# Power_tree_design.net
KiCad netlist of a schematic drawn in Altium Designer
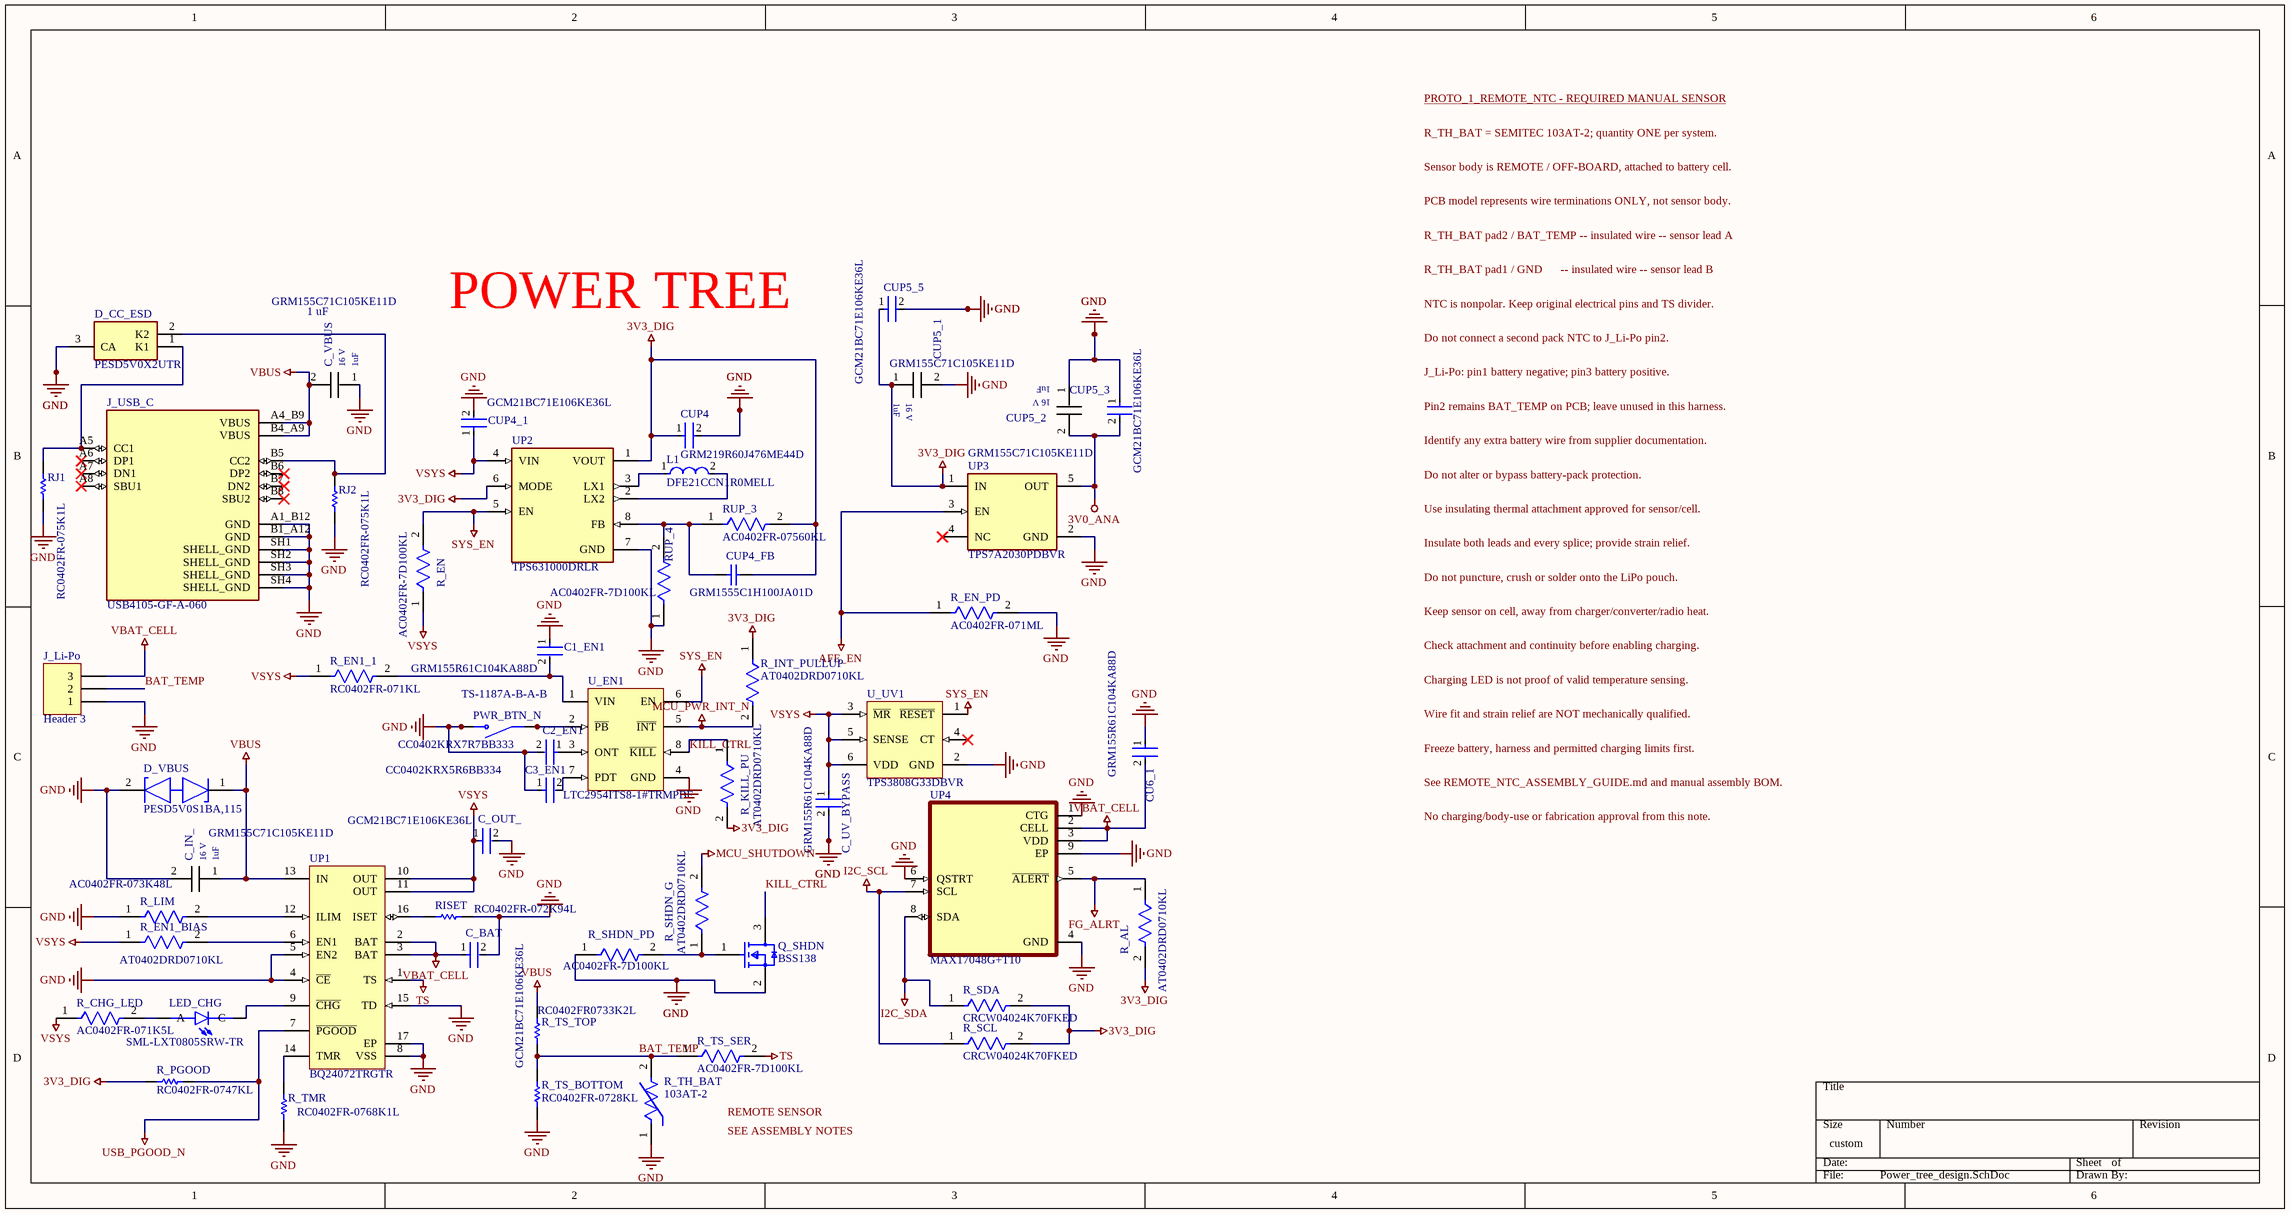
[diagram p0: Power_tree_design.SchDoc]

(export (version "E")
  (design (tool "Eeschema 10.0.6"))
  (components
    (comp (ref "C1_EN1")
      (value "GRM155R61C104KA88D")
      (footprint "96DF66F8-B997-472F-A885-42BCAAE661B2_FP-GRM155-0_05-IPC_C:FP-GRM155-0_05-IPC_C")
      (description "CAP CER 0.1UF 16V X5R 0402")
      (fields (field (name "VOLTAGE") "16V") (field (name "TOLERANCE") "10%"))
      (libsource (lib "EMG_Controlled_R5") (part "EMG_R5_C1_EN1"))
    )
    (comp (ref "C2_EN1")
      (value "CC0402KRX7R7BB333")
      (footprint "C3796861-3712-47DF-AA44-4C1CD1021AF7_FP-CC0402-MFG:FP-CC0402-MFG")
      (description "CAP CER 0.033UF 16V X7R 0402")
      (fields
        (field (name "MANUFACTURER") "YAGEO")
        (field (name "OCTOPART") "https://octopart.com/cc0402krx7r7bb333-yageo-9289202")
      )
      (libsource (lib "EMG_Controlled_R5") (part "EMG_R5_C2_EN1"))
    )
    (comp (ref "C3_EN1")
      (value "CC0402KRX5R6BB334")
      (footprint "C3796861-3712-47DF-AA44-4C1CD1021AF7_FP-CC0402-MFG:FP-CC0402-MFG")
      (description "CAP CER 0.33UF 10V X5R 0402")
      (fields
        (field (name "MANUFACTURER") "YAGEO")
        (field (name "OCTOPART") "https://octopart.com/cc0402krx5r6bb334-yageo-21548561")
      )
      (libsource (lib "EMG_Controlled_R5") (part "EMG_R5_C3_EN1"))
    )
    (comp (ref "CU6_1")
      (value "GRM155R61C104KA88D")
      (footprint "96DF66F8-B997-472F-A885-42BCAAE661B2_FP-GRM155-0_05-IPC_C:FP-GRM155-0_05-IPC_C")
      (description "CAP CER 0.1UF 16V X5R 0402")
      (fields (field (name "VOLTAGE") "16V") (field (name "TOLERANCE") "10%"))
      (libsource (lib "EMG_Controlled_R5") (part "EMG_R5_CU6_1"))
    )
    (comp (ref "CUP4")
      (value "GRM219R60J476ME44D")
      (footprint "C53EA0CA-0507-449B-AA9E-0712004E71D5_FP-GRM219-0_2-0_1-IPC_A:FP-GRM219-0_2-0_1-IPC_A")
      (description "Chip Multilayer Ceramic Capacitors for General Purpose, 0805, 47uF, X5R, 15%, 20%, 6.3V")
      (fields (field (name "TOLERANCE") "20%"))
      (libsource (lib "EMG_Controlled_R5") (part "EMG_R5_CUP4"))
    )
    (comp (ref "CUP4_1")
      (value "GCM21BC71E106KE36L")
      (footprint "936D640C-6583-4BC1-90EC-E059FB2B465D_FP-GCM21B-0_2-e0_2_0_7-MFG:FP-GCM21B-0_2-e0_2_0_7-MFG")
      (description "10 µF ±10% 25V Ceramic Capacitor X7S 0805 (2012 Metric)")
      (libsource (lib "EMG_Controlled_R5") (part "EMG_R5_CUP4_1"))
    )
    (comp (ref "CUP4_FB")
      (value "GRM1555C1H100JA01D")
      (footprint "2E7254C8-59E0-43F9-ABB3-713B229FF2F1_CAPC1005X55X25LL05T10:CAPC1005X55X25LL05T10")
      (fields (field (name "MANUFACTURER") "Murata"))
      (libsource (lib "EMG_Controlled_R5") (part "EMG_R5_CUP4_FB"))
    )
    (comp (ref "CUP5_1")
      (value "GRM155C71C105KE11D")
      (footprint "MURATA_GRM155C71C105KE11D_0:*MURATA_GRM155C71C105KE11D_0")
      (description "Murata GRM155C71C105KE11D: 1 uF 16 V X7S +/-10%, 0402/1005 metric")
      (fields (field (name "MF") "Murata") (field (name "TOLERANCE") "+/-10%"))
      (libsource (lib "EMG_Controlled_R5") (part "EMG_R5_CUP5_1"))
    )
    (comp (ref "CUP5_2")
      (value "GRM155C71C105KE11D")
      (footprint "MURATA_GRM155C71C105KE11D_0:*MURATA_GRM155C71C105KE11D_0")
      (description "Murata GRM155C71C105KE11D: 1 uF 16 V X7S +/-10%, 0402/1005 metric")
      (fields (field (name "MF") "Murata") (field (name "TOLERANCE") "+/-10%"))
      (libsource (lib "EMG_Controlled_R5") (part "EMG_R5_CUP5_2"))
    )
    (comp (ref "CUP5_3")
      (value "GCM21BC71E106KE36L")
      (footprint "936D640C-6583-4BC1-90EC-E059FB2B465D_FP-GCM21B-0_2-e0_2_0_7-MFG:FP-GCM21B-0_2-e0_2_0_7-MFG")
      (description "10 µF ±10% 25V Ceramic Capacitor X7S 0805 (2012 Metric)")
      (libsource (lib "EMG_Controlled_R5") (part "EMG_R5_CUP5_3"))
    )
    (comp (ref "CUP5_5")
      (value "GCM21BC71E106KE36L")
      (footprint "936D640C-6583-4BC1-90EC-E059FB2B465D_FP-GCM21B-0_2-e0_2_0_7-MFG:FP-GCM21B-0_2-e0_2_0_7-MFG")
      (description "10 µF ±10% 25V Ceramic Capacitor X7S 0805 (2012 Metric)")
      (libsource (lib "EMG_Controlled_R5") (part "EMG_R5_CUP5_5"))
    )
    (comp (ref "C_BAT")
      (value "GCM21BC71E106KE36L")
      (footprint "936D640C-6583-4BC1-90EC-E059FB2B465D_FP-GCM21B-0_2-e0_2_0_7-MFG:FP-GCM21B-0_2-e0_2_0_7-MFG")
      (description "10 µF ±10% 25V Ceramic Capacitor X7S 0805 (2012 Metric)")
      (libsource (lib "EMG_Controlled_R5") (part "EMG_R5_C_BAT"))
    )
    (comp (ref "C_IN_")
      (value "GRM155C71C105KE11D")
      (footprint "MURATA_GRM155C71C105KE11D_0:*MURATA_GRM155C71C105KE11D_0")
      (description "Murata GRM155C71C105KE11D: 1 uF 16 V X7S +/-10%, 0402/1005 metric")
      (fields (field (name "MF") "Murata") (field (name "TOLERANCE") "+/-10%"))
      (libsource (lib "EMG_Controlled_R5") (part "EMG_R5_C_IN_"))
    )
    (comp (ref "C_OUT_")
      (value "GCM21BC71E106KE36L")
      (footprint "936D640C-6583-4BC1-90EC-E059FB2B465D_FP-GCM21B-0_2-e0_2_0_7-MFG:FP-GCM21B-0_2-e0_2_0_7-MFG")
      (description "10 µF ±10% 25V Ceramic Capacitor X7S 0805 (2012 Metric)")
      (libsource (lib "EMG_Controlled_R5") (part "EMG_R5_C_OUT_"))
    )
    (comp (ref "C_UV_BYPASS")
      (value "GRM155R61C104KA88D")
      (footprint "96DF66F8-B997-472F-A885-42BCAAE661B2_FP-GRM155-0_05-IPC_C:FP-GRM155-0_05-IPC_C")
      (description "CAP CER 0.1UF 16V X5R 0402")
      (fields (field (name "VOLTAGE") "16V") (field (name "TOLERANCE") "10%"))
      (libsource (lib "EMG_Controlled_R5") (part "EMG_R5_C_UV_BYPASS"))
    )
    (comp (ref "C_VBUS")
      (value "GRM155C71C105KE11D")
      (footprint "MURATA_GRM155C71C105KE11D_0:*MURATA_GRM155C71C105KE11D_0")
      (description "Murata GRM155C71C105KE11D: 1 uF 16 V X7S +/-10%, 0402/1005 metric")
      (fields
        (field (name "MF") "Murata")
        (field (name "ALTIUM_VALUE") "1 uF")
        (field (name "TOLERANCE") "+/-10%")
      )
      (libsource (lib "EMG_Controlled_R5") (part "EMG_R5_C_VBUS"))
    )
    (comp (ref "D_CC_ESD")
      (value "PESD5V0X2UTR")
      (footprint "SamacSys:SOT95P230X100-3N")
      (description "TVS Diode (Uni-directional)")
      (libsource (lib "EMG_Controlled_R5") (part "EMG_R5_D_CC_ESD"))
    )
    (comp (ref "D_VBUS")
      (value "PESD5V0S1BA,115")
      (footprint "45C21C89-16FD-4743-99D5-BE7C796D208F_FP-SOD323-CA-MFG:FP-SOD323-CA-MFG")
      (description "TVS DIODE 5V 14V SOD323")
      (libsource (lib "EMG_Controlled_R5") (part "EMG_R5_D_VBUS"))
    )
    (comp (ref "J_Li-Po")
      (value "Header 3")
      (footprint "Miscellaneous_Connectors_0:HDR1X3")
      (description "Header, 3-Pin")
      (fields (field (name "PUBLISHER") "Altium Limited"))
      (libsource (lib "EMG_Controlled_R5") (part "EMG_R5_J_Li-Po"))
    )
    (comp (ref "J_USB_C")
      (value "USB4105-GF-A-060")
      (footprint "USB4105-GF-A-060_0:GCT_USB4105-GF-A-060")
      (fields (field (name "MF") "Global Connector Technology") (field (name "MP") "USB4105GFA060"))
      (libsource (lib "EMG_Controlled_R5") (part "EMG_R5_J_USB_C"))
    )
    (comp (ref "L1")
      (value "DFE21CCN1R0MELL")
      (footprint "F49AD27E-DF89-41E7-B4E0-151C9F468E9A_FP-DFE21CC_EL-MFG:FP-DFE21CC_EL-MFG")
      (description "FIXED IND 1.0UH 3300MA NONAUTO")
      (libsource (lib "EMG_Controlled_R5") (part "EMG_R5_L1"))
    )
    (comp (ref "LED_CHG")
      (value "SML-LXT0805SRW-TR")
      (footprint "SML-LXT0805SRW-TR_0:LEDC2012X120N")
      (description "Red - LED Indication - Discrete 1.8V 0805 (2012 Metric)")
      (fields (field (name "MF") "Lumex Opto/Components"))
      (libsource (lib "EMG_Controlled_R5") (part "EMG_R5_LED_CHG"))
    )
    (comp (ref "PWR_BTN_N")
      (value "TS-1187A-B-A-B")
      (footprint "TS-1187A-B-A-B_0:SW_TS-1187A-B-A-B")
      (description "SPST 50mA @ 12VDC Top Actuated Round Button 160gf SMD Tactile Switches RoHS")
      (libsource (lib "EMG_Controlled_R5") (part "EMG_R5_PWR_BTN_N"))
    )
    (comp (ref "Q_SHDN")
      (value "BSS138")
      (footprint "37A995D1-DA80-4C84-BCF6-31F59D376AC2_FP-318-08-IPC_B:FP-318-08-IPC_B")
      (description "MOSFET N-CH 50V 220MA SOT-23")
      (libsource (lib "EMG_Controlled_R5") (part "EMG_R5_Q_SHDN"))
    )
    (comp (ref "RISET")
      (value "RC0402FR-072K94L")
      (footprint "D3F9B43C-7553-417F-9DE9-81F21DD543C4_RESC1005X40X25ML05T10:RESC1005X40X25ML05T10")
      (fields (field (name "MANUFACTURER") "Yageo"))
      (libsource (lib "EMG_Controlled_R5") (part "EMG_R5_RISET"))
    )
    (comp (ref "RJ1")
      (value "RC0402FR-075K1L")
      (footprint "3EB15388-1759-44FF-BAE1-1F0823F3E8F1_RESC1005X40X25NL05T10:RESC1005X40X25NL05T10")
      (fields (field (name "MANUFACTURER") "Yageo / Phycomp"))
      (libsource (lib "EMG_Controlled_R5") (part "EMG_R5_RJ1"))
    )
    (comp (ref "RJ2")
      (value "RC0402FR-075K1L")
      (footprint "3EB15388-1759-44FF-BAE1-1F0823F3E8F1_RESC1005X40X25NL05T10:RESC1005X40X25NL05T10")
      (fields (field (name "MANUFACTURER") "Yageo / Phycomp"))
      (libsource (lib "EMG_Controlled_R5") (part "EMG_R5_RJ2"))
    )
    (comp (ref "RUP_3")
      (value "AC0402FR-07560KL")
      (footprint "1CBBEC27-AD79-48E8-A701-2E235EA9F8F2_FP-AC0402-IPC_A:FP-AC0402-IPC_A")
      (description "RES 560kΩ ±1% 0.063W 0402")
      (fields (field (name "TOLERANCE") "1%"))
      (libsource (lib "EMG_Controlled_R5") (part "EMG_R5_RUP_3"))
    )
    (comp (ref "RUP_4")
      (value "AC0402FR-7D100KL")
      (footprint "7D606042-220B-45EE-95DD-CA1A974E4C0D_FP-AC0402-MFG:FP-AC0402-MFG")
      (description "AC0402 100KΩ 0.0625W 1.00%")
      (fields
        (field (name "MANUFACTURER") "Yageo")
        (field (name "OCTOPART") "https://octopart.com/ac0402fr-7d100kl-yageo-91024821")
      )
      (libsource (lib "EMG_Controlled_R5") (part "EMG_R5_RUP_4"))
    )
    (comp (ref "R_AL")
      (value "AT0402DRD0710KL")
      (footprint "3CC89DB5-6984-43B7-8501-EF32E845BDBA_FP-AT0402-IPC_A:FP-AT0402-IPC_A")
      (description "Thin Film Chip Resistors Automotive Grade 10kΩ 0.5% 25ppm/°C 0402")
      (fields (field (name "TOLERANCE") "0.5%"))
      (libsource (lib "EMG_Controlled_R5") (part "EMG_R5_R_AL"))
    )
    (comp (ref "R_CHG_LED")
      (value "AC0402FR-071K5L")
      (footprint "46E5B6C0-52D2-4F38-862C-679C4EE84A1B_FP-AC0402-MFG:FP-AC0402-MFG")
      (description "RES 1.5kΩ ±1% 0.063W 0402")
      (fields (field (name "TOLERANCE") "1%"))
      (libsource (lib "EMG_Controlled_R5") (part "EMG_R5_R_CHG_LED"))
    )
    (comp (ref "R_EN")
      (value "AC0402FR-7D100KL")
      (footprint "7D606042-220B-45EE-95DD-CA1A974E4C0D_FP-AC0402-MFG:FP-AC0402-MFG")
      (description "AC0402 100KΩ 0.0625W 1.00%")
      (fields
        (field (name "MANUFACTURER") "Yageo")
        (field (name "OCTOPART") "https://octopart.com/ac0402fr-7d100kl-yageo-91024821")
      )
      (libsource (lib "EMG_Controlled_R5") (part "EMG_R5_R_EN"))
    )
    (comp (ref "R_EN1_1")
      (value "RC0402FR-071KL")
      (footprint "2B8210F7-5455-4644-979C-D7D0D217EEB4_FP-RC0402-0_4-IPC_A:FP-RC0402-0_4-IPC_A")
      (description "RES 1K OHM 1% 1/16W 0402")
      (fields (field (name "TOLERANCE") "1%"))
      (libsource (lib "EMG_Controlled_R5") (part "EMG_R5_R_EN1_1"))
    )
    (comp (ref "R_EN1_BIAS")
      (value "AT0402DRD0710KL")
      (footprint "3CC89DB5-6984-43B7-8501-EF32E845BDBA_FP-AT0402-IPC_A:FP-AT0402-IPC_A")
      (description "Thin Film Chip Resistors Automotive Grade 10kΩ 0.5% 25ppm/°C 0402")
      (fields (field (name "TOLERANCE") "0.5%"))
      (libsource (lib "EMG_Controlled_R5") (part "EMG_R5_R_EN1_BIAS"))
    )
    (comp (ref "R_EN_PD")
      (value "AC0402FR-071ML")
      (footprint "1CBBEC27-AD79-48E8-A701-2E235EA9F8F2_FP-AC0402-IPC_A:FP-AC0402-IPC_A")
      (description "RES 1MΩ ±1% 0.063W 0402")
      (fields (field (name "TOLERANCE") "1%"))
      (libsource (lib "EMG_Controlled_R5") (part "EMG_R5_R_EN_PD"))
    )
    (comp (ref "R_INT_PULLUP")
      (value "AT0402DRD0710KL")
      (footprint "3CC89DB5-6984-43B7-8501-EF32E845BDBA_FP-AT0402-IPC_A:FP-AT0402-IPC_A")
      (description "Thin Film Chip Resistors Automotive Grade 10kΩ 0.5% 25ppm/°C 0402")
      (fields (field (name "TOLERANCE") "0.5%"))
      (libsource (lib "EMG_Controlled_R5") (part "EMG_R5_R_INT_PULLUP"))
    )
    (comp (ref "R_KILL_PU")
      (value "AT0402DRD0710KL")
      (footprint "3CC89DB5-6984-43B7-8501-EF32E845BDBA_FP-AT0402-IPC_A:FP-AT0402-IPC_A")
      (description "Thin Film Chip Resistors Automotive Grade 10kΩ 0.5% 25ppm/°C 0402")
      (fields (field (name "TOLERANCE") "0.5%"))
      (libsource (lib "EMG_Controlled_R5") (part "EMG_R5_R_KILL_PU"))
    )
    (comp (ref "R_LIM")
      (value "AC0402FR-073K48L")
      (footprint "46E5B6C0-52D2-4F38-862C-679C4EE84A1B_FP-AC0402-MFG:FP-AC0402-MFG")
      (description "RES 3.48kΩ ±1% 0.063W 0402")
      (fields (field (name "TOLERANCE") "1%"))
      (libsource (lib "EMG_Controlled_R5") (part "EMG_R5_R_LIM"))
    )
    (comp (ref "R_PGOOD")
      (value "RC0402FR-0747KL")
      (footprint "D3F9B43C-7553-417F-9DE9-81F21DD543C4_RESC1005X40X25ML05T10:RESC1005X40X25ML05T10")
      (fields (field (name "MANUFACTURER") "Yageo / Phycomp"))
      (libsource (lib "EMG_Controlled_R5") (part "EMG_R5_R_PGOOD"))
    )
    (comp (ref "R_SCL")
      (value "CRCW04024K70FKED")
      (footprint "65C1111B-6B34-43D4-A771-7B0D0C42AE37_FP-CRCW0402-e3-IPC_B:FP-CRCW0402-e3-IPC_B")
      (description "RES Thick Film, 4.7kΩ, 1%, 0.063W, 100ppm/°C, 0402")
      (fields (field (name "TOLERANCE") "1%"))
      (libsource (lib "EMG_Controlled_R5") (part "EMG_R5_R_SCL"))
    )
    (comp (ref "R_SDA")
      (value "CRCW04024K70FKED")
      (footprint "65C1111B-6B34-43D4-A771-7B0D0C42AE37_FP-CRCW0402-e3-IPC_B:FP-CRCW0402-e3-IPC_B")
      (description "RES Thick Film, 4.7kΩ, 1%, 0.063W, 100ppm/°C, 0402")
      (fields (field (name "TOLERANCE") "1%"))
      (libsource (lib "EMG_Controlled_R5") (part "EMG_R5_R_SDA"))
    )
    (comp (ref "R_SHDN_G")
      (value "AT0402DRD0710KL")
      (footprint "3CC89DB5-6984-43B7-8501-EF32E845BDBA_FP-AT0402-IPC_A:FP-AT0402-IPC_A")
      (description "Thin Film Chip Resistors Automotive Grade 10kΩ 0.5% 25ppm/°C 0402")
      (fields (field (name "TOLERANCE") "0.5%"))
      (libsource (lib "EMG_Controlled_R5") (part "EMG_R5_R_SHDN_G"))
    )
    (comp (ref "R_SHDN_PD")
      (value "AC0402FR-7D100KL")
      (footprint "7D606042-220B-45EE-95DD-CA1A974E4C0D_FP-AC0402-MFG:FP-AC0402-MFG")
      (description "AC0402 100KΩ 0.0625W 1.00%")
      (fields
        (field (name "MANUFACTURER") "Yageo")
        (field (name "OCTOPART") "https://octopart.com/ac0402fr-7d100kl-yageo-91024821")
      )
      (libsource (lib "EMG_Controlled_R5") (part "EMG_R5_R_SHDN_PD"))
    )
    (comp (ref "R_TH_BAT")
      (value "103AT-2")
      (footprint "EMG_Remote_NTC_Terminals:EMG_REMOTE_NTC_TERMINALS_2P")
      (description "Required remote cell-temperature NTC; manual off-board assembly")
      (fields (field (name "MANUFACTURER") "SEMITEC Corporation") (field (name "TOLERANCE") "+/-1% at 25 C"))
      (libsource (lib "EMG_Controlled_R5") (part "EMG_R5_R_TH_BAT"))
    )
    (comp (ref "R_TMR")
      (value "RC0402FR-0768K1L")
      (footprint "D3F9B43C-7553-417F-9DE9-81F21DD543C4_RESC1005X40X25ML05T10:RESC1005X40X25ML05T10")
      (fields (field (name "MANUFACTURER") "Yageo / Phycomp"))
      (libsource (lib "EMG_Controlled_R5") (part "EMG_R5_R_TMR"))
    )
    (comp (ref "R_TS_BOTTOM")
      (value "RC0402FR-0728KL")
      (footprint "3EB15388-1759-44FF-BAE1-1F0823F3E8F1_RESC1005X40X25NL05T10:RESC1005X40X25NL05T10")
      (fields (field (name "MANUFACTURER") "Yageo"))
      (libsource (lib "EMG_Controlled_R5") (part "EMG_R5_R_TS_BOTTOM"))
    )
    (comp (ref "R_TS_SER")
      (value "AC0402FR-7D100KL")
      (footprint "7D606042-220B-45EE-95DD-CA1A974E4C0D_FP-AC0402-MFG:FP-AC0402-MFG")
      (description "AC0402 100KΩ 0.0625W 1.00%")
      (fields
        (field (name "MANUFACTURER") "Yageo")
        (field (name "OCTOPART") "https://octopart.com/ac0402fr-7d100kl-yageo-91024821")
      )
      (libsource (lib "EMG_Controlled_R5") (part "EMG_R5_R_TS_SER"))
    )
    (comp (ref "R_TS_TOP")
      (value "RC0402FR0733K2L")
      (footprint "3EB15388-1759-44FF-BAE1-1F0823F3E8F1_RESC1005X40X25NL05T10:RESC1005X40X25NL05T10")
      (fields (field (name "MANUFACTURER") "Yageo / Phycomp"))
      (libsource (lib "EMG_Controlled_R5") (part "EMG_R5_R_TS_TOP"))
    )
    (comp (ref "UP1")
      (value "BQ24072TRGTR")
      (footprint "E8847AB5-6F42-426A-8B44-B46A8033A4A6_RGT0016C_V:RGT0016C_V")
      (fields (field (name "MANUFACTURER") "Texas Instruments"))
      (libsource (lib "EMG_Controlled_R5") (part "EMG_R5_UP1"))
    )
    (comp (ref "UP2")
      (value "TPS631000DRLR")
      (footprint "TPS631000DRLR_0:SOT50P160X60-8N")
      (description "1.5-A output current, high-power-density buck-boost converter")
      (fields (field (name "MF") "Texas Instruments"))
      (libsource (lib "EMG_Controlled_R5") (part "EMG_R5_UP2"))
    )
    (comp (ref "UP3")
      (value "TPS7A2030PDBVR")
      (footprint "799007F4-6CCC-4692-897B-9164B654F9CD_FP-DBV0005A-IPC_C:FP-DBV0005A-IPC_C")
      (description "IC REG LINEAR 3V 300MA SOT23-5")
      (libsource (lib "EMG_Controlled_R5") (part "EMG_R5_UP3"))
    )
    (comp (ref "UP4")
      (value "MAX17048G+T10")
      (footprint "MAX17048G_T10_0:SON50P200X200X80-9N")
      (description "3ÂµA 1-Cell/2-Cell Fuel Gauge with ModelGauge")
      (fields (field (name "MF") "Analog Devices"))
      (libsource (lib "EMG_Controlled_R5") (part "EMG_R5_UP4"))
    )
    (comp (ref "U_EN1")
      (value "LTC2954ITS8-1#TRMPBF")
      (footprint "ADDD786E-880E-4859-B2C3-CD7A0A6A9F96_LT-TS8-8-TSOT-23_V:LT-TS8-8-TSOT-23_V")
      (fields (field (name "MANUFACTURER") "Linear Technology"))
      (libsource (lib "EMG_Controlled_R5") (part "EMG_R5_U_EN1"))
    )
    (comp (ref "U_UV1")
      (value "TPS3808G33DBVR")
      (footprint "FDB5B680-CA48-4746-AF97-B60256D4C87B_DBV0006A_L:DBV0006A_L")
      (fields (field (name "MANUFACTURER") "Texas Instruments"))
      (libsource (lib "EMG_Controlled_R5") (part "EMG_R5_U_UV1"))
    )
  )
  (nets
    (net (code "1") (name "/BAT_TEMP") (class "Default")
      (node (ref "J_Li-Po") (pin "2") (pinfunction "2_2") (pintype "passive"))
      (node (ref "R_TH_BAT") (pin "2") (pinfunction "2_2") (pintype "passive"))
      (node (ref "R_TS_BOTTOM") (pin "2") (pinfunction "2_2") (pintype "passive"))
      (node (ref "R_TS_SER") (pin "1") (pinfunction "1_1") (pintype "passive"))
      (node (ref "R_TS_TOP") (pin "1") (pinfunction "1_1") (pintype "passive"))
    )
    (net (code "2") (name "/KILL_CTRL") (class "Default")
      (node (ref "Q_SHDN") (pin "3") (pinfunction "D_3") (pintype "passive"))
      (node (ref "R_KILL_PU") (pin "1") (pinfunction "1_1") (pintype "passive"))
      (node (ref "U_EN1") (pin "8") (pinfunction "~{KILL}_8") (pintype "input"))
    )
    (net (code "3") (name "3V0_ANA") (class "Default")
      (node (ref "CUP5_2") (pin "2") (pinfunction "2_2") (pintype "passive"))
      (node (ref "CUP5_3") (pin "2") (pinfunction "2_2") (pintype "passive"))
      (node (ref "UP3") (pin "5") (pinfunction "OUT_5") (pintype "power_in"))
    )
    (net (code "4") (name "3V3_DIG") (class "Default")
      (node (ref "CUP4") (pin "1") (pinfunction "1_1") (pintype "passive"))
      (node (ref "CUP4_FB") (pin "2") (pinfunction "2_2") (pintype "passive"))
      (node (ref "CUP5_1") (pin "1") (pinfunction "1_1") (pintype "passive"))
      (node (ref "CUP5_5") (pin "1") (pinfunction "1_1") (pintype "passive"))
      (node (ref "RUP_3") (pin "2") (pinfunction "2_2") (pintype "passive"))
      (node (ref "R_AL") (pin "2") (pinfunction "2_2") (pintype "passive"))
      (node (ref "R_INT_PULLUP") (pin "1") (pinfunction "1_1") (pintype "passive"))
      (node (ref "R_KILL_PU") (pin "2") (pinfunction "2_2") (pintype "passive"))
      (node (ref "R_PGOOD") (pin "2") (pinfunction "2_2") (pintype "passive"))
      (node (ref "R_SCL") (pin "2") (pinfunction "2_2") (pintype "passive"))
      (node (ref "R_SDA") (pin "2") (pinfunction "2_2") (pintype "passive"))
      (node (ref "UP2") (pin "1") (pinfunction "VOUT_1") (pintype "power_in"))
      (node (ref "UP2") (pin "6") (pinfunction "MODE_6") (pintype "input"))
      (node (ref "UP3") (pin "1") (pinfunction "IN_1") (pintype "power_in"))
    )
    (net (code "5") (name "AFE_EN") (class "Default")
      (node (ref "R_EN_PD") (pin "1") (pinfunction "1_1") (pintype "passive"))
      (node (ref "UP3") (pin "3") (pinfunction "EN_3") (pintype "input"))
    )
    (net (code "6") (name "FG_ALRT") (class "Default")
      (node (ref "R_AL") (pin "1") (pinfunction "1_1") (pintype "passive"))
      (node (ref "UP4") (pin "5") (pinfunction "~{ALERT}_5") (pintype "output"))
    )
    (net (code "7") (name "GND") (class "Default")
      (node (ref "C1_EN1") (pin "1") (pinfunction "1_1") (pintype "passive"))
      (node (ref "C2_EN1") (pin "2") (pinfunction "2_2") (pintype "passive"))
      (node (ref "C3_EN1") (pin "1") (pinfunction "1_1") (pintype "passive"))
      (node (ref "CU6_1") (pin "1") (pinfunction "1_1") (pintype "passive"))
      (node (ref "CUP4") (pin "2") (pinfunction "2_2") (pintype "passive"))
      (node (ref "CUP4_1") (pin "2") (pinfunction "2_2") (pintype "passive"))
      (node (ref "CUP5_1") (pin "2") (pinfunction "2_2") (pintype "passive"))
      (node (ref "CUP5_2") (pin "1") (pinfunction "1_1") (pintype "passive"))
      (node (ref "CUP5_3") (pin "1") (pinfunction "1_1") (pintype "passive"))
      (node (ref "CUP5_5") (pin "2") (pinfunction "2_2") (pintype "passive"))
      (node (ref "C_BAT") (pin "2") (pinfunction "2_2") (pintype "passive"))
      (node (ref "C_IN_") (pin "2") (pinfunction "2_2") (pintype "passive"))
      (node (ref "C_OUT_") (pin "2") (pinfunction "2_2") (pintype "passive"))
      (node (ref "C_UV_BYPASS") (pin "2") (pinfunction "2_2") (pintype "passive"))
      (node (ref "C_VBUS") (pin "1") (pinfunction "1_1") (pintype "passive"))
      (node (ref "D_CC_ESD") (pin "3") (pinfunction "CA_3") (pintype "passive"))
      (node (ref "D_VBUS") (pin "2") (pinfunction "K2_2") (pintype "passive"))
      (node (ref "J_Li-Po") (pin "1") (pinfunction "1_1") (pintype "passive"))
      (node (ref "J_USB_C") (pin "A1_B12") (pinfunction "GND_A1_B12") (pintype "power_in"))
      (node (ref "J_USB_C") (pin "B1_A12") (pinfunction "GND_B1_A12") (pintype "power_in"))
      (node (ref "J_USB_C") (pin "SH1") (pinfunction "SHELL_GND_SH1") (pintype "power_in"))
      (node (ref "J_USB_C") (pin "SH2") (pinfunction "SHELL_GND_SH2") (pintype "power_in"))
      (node (ref "J_USB_C") (pin "SH3") (pinfunction "SHELL_GND_SH3") (pintype "power_in"))
      (node (ref "J_USB_C") (pin "SH4") (pinfunction "SHELL_GND_SH4") (pintype "power_in"))
      (node (ref "PWR_BTN_N") (pin "C") (pinfunction "NO_C") (pintype "passive"))
      (node (ref "PWR_BTN_N") (pin "D") (pinfunction "NO_D") (pintype "passive"))
      (node (ref "Q_SHDN") (pin "2") (pinfunction "S_2") (pintype "passive"))
      (node (ref "RISET") (pin "2") (pinfunction "2_2") (pintype "passive"))
      (node (ref "RJ1") (pin "1") (pinfunction "1_1") (pintype "passive"))
      (node (ref "RJ2") (pin "1") (pinfunction "1_1") (pintype "passive"))
      (node (ref "RUP_4") (pin "1") (pinfunction "1_1") (pintype "passive"))
      (node (ref "R_EN_PD") (pin "2") (pinfunction "2_2") (pintype "passive"))
      (node (ref "R_LIM") (pin "1") (pinfunction "1_1") (pintype "passive"))
      (node (ref "R_SHDN_PD") (pin "1") (pinfunction "1_1") (pintype "passive"))
      (node (ref "R_TH_BAT") (pin "1") (pinfunction "1_1") (pintype "passive"))
      (node (ref "R_TMR") (pin "1") (pinfunction "1_1") (pintype "passive"))
      (node (ref "R_TS_BOTTOM") (pin "1") (pinfunction "1_1") (pintype "passive"))
      (node (ref "UP1") (pin "15") (pinfunction "TD_15") (pintype "input"))
      (node (ref "UP1") (pin "17") (pinfunction "EP_17") (pintype "power_in"))
      (node (ref "UP1") (pin "4") (pinfunction "~{CE}_4") (pintype "input"))
      (node (ref "UP1") (pin "5") (pinfunction "EN2_5") (pintype "input"))
      (node (ref "UP1") (pin "8") (pinfunction "VSS_8") (pintype "power_in"))
      (node (ref "UP2") (pin "7") (pinfunction "GND_7") (pintype "power_in"))
      (node (ref "UP3") (pin "2") (pinfunction "GND_2") (pintype "power_in"))
      (node (ref "UP4") (pin "1") (pinfunction "CTG_1") (pintype "power_in"))
      (node (ref "UP4") (pin "4") (pinfunction "GND_4") (pintype "power_in"))
      (node (ref "UP4") (pin "6") (pinfunction "QSTRT_6") (pintype "input"))
      (node (ref "UP4") (pin "9") (pinfunction "EP_9") (pintype "power_in"))
      (node (ref "U_EN1") (pin "4") (pinfunction "GND_4") (pintype "power_in"))
      (node (ref "U_UV1") (pin "2") (pinfunction "GND_2") (pintype "power_in"))
    )
    (net (code "8") (name "I2C_SCL") (class "Default")
      (node (ref "R_SCL") (pin "1") (pinfunction "1_1") (pintype "passive"))
      (node (ref "UP4") (pin "7") (pinfunction "SCL_7") (pintype "input"))
    )
    (net (code "9") (name "I2C_SDA") (class "Default")
      (node (ref "R_SDA") (pin "1") (pinfunction "1_1") (pintype "passive"))
      (node (ref "UP4") (pin "8") (pinfunction "SDA_8") (pintype "bidirectional"))
    )
    (net (code "10") (name "MCU_PWR_INT_N") (class "Default")
      (node (ref "R_INT_PULLUP") (pin "2") (pinfunction "2_2") (pintype "passive"))
      (node (ref "U_EN1") (pin "5") (pinfunction "~{INT}_5") (pintype "open_collector"))
    )
    (net (code "11") (name "MCU_SHUTDOWN") (class "Default")
      (node (ref "R_SHDN_G") (pin "2") (pinfunction "2_2") (pintype "passive"))
    )
    (net (code "12") (name "Net-(D_CC_ESD-K1)") (class "Default")
      (node (ref "D_CC_ESD") (pin "1") (pinfunction "K1_1") (pintype "passive"))
      (node (ref "J_USB_C") (pin "A5") (pinfunction "CC1_A5") (pintype "bidirectional"))
      (node (ref "RJ1") (pin "2") (pinfunction "2_2") (pintype "passive"))
    )
    (net (code "13") (name "Net-(D_CC_ESD-K2)") (class "Default")
      (node (ref "D_CC_ESD") (pin "2") (pinfunction "K2_2") (pintype "passive"))
      (node (ref "J_USB_C") (pin "B5") (pinfunction "CC2_B5") (pintype "bidirectional"))
      (node (ref "RJ2") (pin "2") (pinfunction "2_2") (pintype "passive"))
    )
    (net (code "14") (name "Net-(LED_CHG-PadA)") (class "Default")
      (node (ref "LED_CHG") (pin "A") (pinfunction "A_A") (pintype "passive"))
      (node (ref "R_CHG_LED") (pin "2") (pinfunction "2_2") (pintype "passive"))
    )
    (net (code "15") (name "Net-(Q_SHDN-G)") (class "Default")
      (node (ref "Q_SHDN") (pin "1") (pinfunction "G_1") (pintype "passive"))
      (node (ref "R_SHDN_G") (pin "1") (pinfunction "1_1") (pintype "passive"))
      (node (ref "R_SHDN_PD") (pin "2") (pinfunction "2_2") (pintype "passive"))
    )
    (net (code "16") (name "Net-(UP1-EN1)") (class "Default")
      (node (ref "R_EN1_BIAS") (pin "2") (pinfunction "2_2") (pintype "passive"))
      (node (ref "UP1") (pin "6") (pinfunction "EN1_6") (pintype "input"))
    )
    (net (code "17") (name "Net-(UP1-ILIM)") (class "Default")
      (node (ref "R_LIM") (pin "2") (pinfunction "2_2") (pintype "passive"))
      (node (ref "UP1") (pin "12") (pinfunction "ILIM_12") (pintype "input"))
    )
    (net (code "18") (name "Net-(UP1-ISET)") (class "Default")
      (node (ref "RISET") (pin "1") (pinfunction "1_1") (pintype "passive"))
      (node (ref "UP1") (pin "16") (pinfunction "ISET_16") (pintype "bidirectional"))
    )
    (net (code "19") (name "Net-(UP1-TMR)") (class "Default")
      (node (ref "R_TMR") (pin "2") (pinfunction "2_2") (pintype "passive"))
      (node (ref "UP1") (pin "14") (pinfunction "TMR_14") (pintype "passive"))
    )
    (net (code "20") (name "Net-(UP1-~{CHG})") (class "Default")
      (node (ref "LED_CHG") (pin "C") (pinfunction "C_C") (pintype "passive"))
      (node (ref "UP1") (pin "9") (pinfunction "~{CHG}_9") (pintype "tri_state"))
    )
    (net (code "21") (name "Net-(UP2-FB)") (class "Default")
      (node (ref "CUP4_FB") (pin "1") (pinfunction "1_1") (pintype "passive"))
      (node (ref "RUP_3") (pin "1") (pinfunction "1_1") (pintype "passive"))
      (node (ref "RUP_4") (pin "2") (pinfunction "2_2") (pintype "passive"))
      (node (ref "UP2") (pin "8") (pinfunction "FB_8") (pintype "input"))
    )
    (net (code "22") (name "Net-(UP2-LX1)") (class "Default")
      (node (ref "L1") (pin "1") (pinfunction "1_1") (pintype "passive"))
      (node (ref "UP2") (pin "3") (pinfunction "LX1_3") (pintype "output"))
    )
    (net (code "23") (name "Net-(UP2-LX2)") (class "Default")
      (node (ref "L1") (pin "2") (pinfunction "2_2") (pintype "passive"))
      (node (ref "UP2") (pin "2") (pinfunction "LX2_2") (pintype "output"))
    )
    (net (code "24") (name "Net-(U_EN1-ONT)") (class "Default")
      (node (ref "C2_EN1") (pin "1") (pinfunction "1_1") (pintype "passive"))
      (node (ref "U_EN1") (pin "3") (pinfunction "ONT_3") (pintype "input"))
    )
    (net (code "25") (name "Net-(U_EN1-PDT)") (class "Default")
      (node (ref "C3_EN1") (pin "2") (pinfunction "2_2") (pintype "passive"))
      (node (ref "U_EN1") (pin "7") (pinfunction "PDT_7") (pintype "input"))
    )
    (net (code "26") (name "Net-(U_EN1-VIN)") (class "Default")
      (node (ref "C1_EN1") (pin "2") (pinfunction "2_2") (pintype "passive"))
      (node (ref "R_EN1_1") (pin "2") (pinfunction "2_2") (pintype "passive"))
      (node (ref "U_EN1") (pin "1") (pinfunction "VIN_1") (pintype "power_in"))
    )
    (net (code "27") (name "Net-(U_EN1-~{PB})") (class "Default")
      (node (ref "PWR_BTN_N") (pin "A") (pinfunction "COM_A") (pintype "passive"))
      (node (ref "PWR_BTN_N") (pin "B") (pinfunction "COM_B") (pintype "passive"))
      (node (ref "U_EN1") (pin "2") (pinfunction "~{PB}_2") (pintype "input"))
    )
    (net (code "28") (name "SYS_EN") (class "Default")
      (node (ref "R_EN") (pin "2") (pinfunction "2_2") (pintype "passive"))
      (node (ref "UP2") (pin "5") (pinfunction "EN_5") (pintype "input"))
      (node (ref "U_EN1") (pin "6") (pinfunction "EN_6") (pintype "open_collector"))
      (node (ref "U_UV1") (pin "1") (pinfunction "~{RESET}_1") (pintype "tri_state"))
    )
    (net (code "29") (name "TS") (class "Default")
      (node (ref "R_TS_SER") (pin "2") (pinfunction "2_2") (pintype "passive"))
      (node (ref "UP1") (pin "1") (pinfunction "TS_1") (pintype "input"))
    )
    (net (code "30") (name "USB_PGOOD_N") (class "Default")
      (node (ref "R_PGOOD") (pin "1") (pinfunction "1_1") (pintype "passive"))
      (node (ref "UP1") (pin "7") (pinfunction "~{PGOOD}_7") (pintype "tri_state"))
    )
    (net (code "31") (name "VBAT_CELL") (class "Default")
      (node (ref "CU6_1") (pin "2") (pinfunction "2_2") (pintype "passive"))
      (node (ref "C_BAT") (pin "1") (pinfunction "1_1") (pintype "passive"))
      (node (ref "J_Li-Po") (pin "3") (pinfunction "3_3") (pintype "passive"))
      (node (ref "UP1") (pin "2") (pinfunction "BAT_2") (pintype "power_in"))
      (node (ref "UP1") (pin "3") (pinfunction "BAT_3") (pintype "power_in"))
      (node (ref "UP4") (pin "2") (pinfunction "CELL_2") (pintype "power_in"))
      (node (ref "UP4") (pin "3") (pinfunction "VDD_3") (pintype "power_in"))
    )
    (net (code "32") (name "VBUS") (class "Default")
      (node (ref "C_IN_") (pin "1") (pinfunction "1_1") (pintype "passive"))
      (node (ref "C_VBUS") (pin "2") (pinfunction "2_2") (pintype "passive"))
      (node (ref "D_VBUS") (pin "1") (pinfunction "K1_1") (pintype "passive"))
      (node (ref "J_USB_C") (pin "A4_B9") (pinfunction "VBUS_A4_B9") (pintype "power_in"))
      (node (ref "J_USB_C") (pin "B4_A9") (pinfunction "VBUS_B4_A9") (pintype "power_in"))
      (node (ref "R_TS_TOP") (pin "2") (pinfunction "2_2") (pintype "passive"))
      (node (ref "UP1") (pin "13") (pinfunction "IN_13") (pintype "power_in"))
    )
    (net (code "33") (name "VSYS") (class "Default")
      (node (ref "CUP4_1") (pin "1") (pinfunction "1_1") (pintype "passive"))
      (node (ref "C_OUT_") (pin "1") (pinfunction "1_1") (pintype "passive"))
      (node (ref "C_UV_BYPASS") (pin "1") (pinfunction "1_1") (pintype "passive"))
      (node (ref "R_CHG_LED") (pin "1") (pinfunction "1_1") (pintype "passive"))
      (node (ref "R_EN") (pin "1") (pinfunction "1_1") (pintype "passive"))
      (node (ref "R_EN1_1") (pin "1") (pinfunction "1_1") (pintype "passive"))
      (node (ref "R_EN1_BIAS") (pin "1") (pinfunction "1_1") (pintype "passive"))
      (node (ref "UP1") (pin "10") (pinfunction "OUT_10") (pintype "power_in"))
      (node (ref "UP1") (pin "11") (pinfunction "OUT_11") (pintype "power_in"))
      (node (ref "UP2") (pin "4") (pinfunction "VIN_4") (pintype "input"))
      (node (ref "U_UV1") (pin "3") (pinfunction "~{MR}_3") (pintype "input"))
      (node (ref "U_UV1") (pin "5") (pinfunction "SENSE_5") (pintype "input"))
      (node (ref "U_UV1") (pin "6") (pinfunction "VDD_6") (pintype "power_in"))
    )
    (net (code "34") (name "unconnected-(J_USB_C-DN1-PadA7)") (class "Default")
      (node (ref "J_USB_C") (pin "A7") (pinfunction "DN1_A7") (pintype "bidirectional+no_connect"))
    )
    (net (code "35") (name "unconnected-(J_USB_C-DN2-PadB7)") (class "Default")
      (node (ref "J_USB_C") (pin "B7") (pinfunction "DN2_B7") (pintype "bidirectional+no_connect"))
    )
    (net (code "36") (name "unconnected-(J_USB_C-DP1-PadA6)") (class "Default")
      (node (ref "J_USB_C") (pin "A6") (pinfunction "DP1_A6") (pintype "bidirectional+no_connect"))
    )
    (net (code "37") (name "unconnected-(J_USB_C-DP2-PadB6)") (class "Default")
      (node (ref "J_USB_C") (pin "B6") (pinfunction "DP2_B6") (pintype "bidirectional+no_connect"))
    )
    (net (code "38") (name "unconnected-(J_USB_C-SBU1-PadA8)") (class "Default")
      (node (ref "J_USB_C") (pin "A8") (pinfunction "SBU1_A8") (pintype "bidirectional+no_connect"))
    )
    (net (code "39") (name "unconnected-(J_USB_C-SBU2-PadB8)") (class "Default")
      (node (ref "J_USB_C") (pin "B8") (pinfunction "SBU2_B8") (pintype "bidirectional+no_connect"))
    )
    (net (code "40") (name "unconnected-(UP3-NC-Pad4)") (class "Default")
      (node (ref "UP3") (pin "4") (pinfunction "NC_4") (pintype "passive+no_connect"))
    )
    (net (code "41") (name "unconnected-(U_UV1-CT-Pad4)") (class "Default")
      (node (ref "U_UV1") (pin "4") (pinfunction "CT_4") (pintype "input+no_connect"))
    )
  )
)
